# DigitalIO.net
KiCad netlist of a schematic drawn in EAGLE
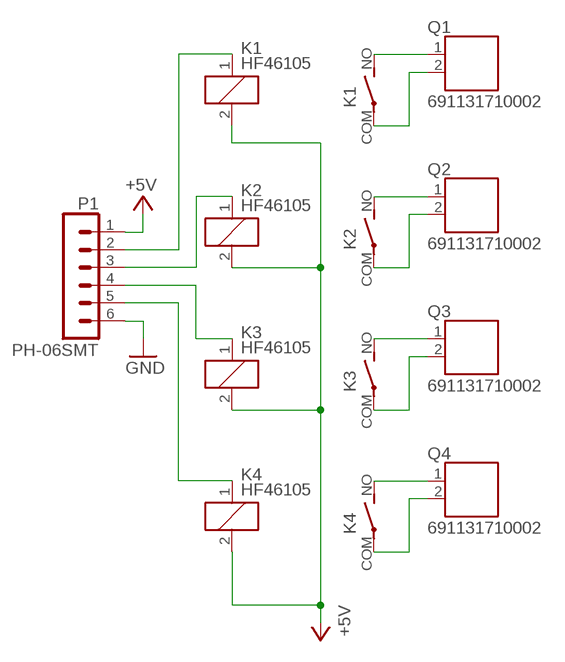
[diagram p0: schematic, sheet 1]

(export (version "E")
  (design (tool "Eeschema 10.0.6"))
  (components
    (comp (ref "K1")
      (value "HF46105")
      (footprint "eagle-import:HF46")
      (libsource (lib "eagle-import") (part "HF46?105"))
    )
    (comp (ref "K2")
      (value "HF46105")
      (footprint "eagle-import:HF46")
      (libsource (lib "eagle-import") (part "HF46?105"))
    )
    (comp (ref "K3")
      (value "HF46105")
      (footprint "eagle-import:HF46")
      (libsource (lib "eagle-import") (part "HF46?105"))
    )
    (comp (ref "K4")
      (value "HF46105")
      (footprint "eagle-import:HF46")
      (libsource (lib "eagle-import") (part "HF46?105"))
    )
    (comp (ref "P1")
      (value "PH-06SMT")
      (footprint "eagle-import:S6B-PH-SM4")
      (libsource (lib "eagle-import") (part "PH-06SMT"))
    )
    (comp (ref "Q1")
      (value "691131710002")
      (footprint "eagle-import:691131710002")
      (libsource (lib "eagle-import") (part "691131710002"))
    )
    (comp (ref "Q2")
      (value "691131710002")
      (footprint "eagle-import:691131710002")
      (libsource (lib "eagle-import") (part "691131710002"))
    )
    (comp (ref "Q3")
      (value "691131710002")
      (footprint "eagle-import:691131710002")
      (libsource (lib "eagle-import") (part "691131710002"))
    )
    (comp (ref "Q4")
      (value "691131710002")
      (footprint "eagle-import:691131710002")
      (libsource (lib "eagle-import") (part "691131710002"))
    )
  )
  (nets
    (net (code "1") (name "+5V") (class "Default")
      (node (ref "K1") (pin "2") (pinfunction "2_2") (pintype "passive"))
      (node (ref "K2") (pin "2") (pinfunction "2_2") (pintype "passive"))
      (node (ref "K3") (pin "2") (pinfunction "2_2") (pintype "passive"))
      (node (ref "K4") (pin "2") (pinfunction "2_2") (pintype "passive"))
      (node (ref "P1") (pin "1") (pinfunction "1_1") (pintype "passive"))
    )
    (net (code "2") (name "GND") (class "Default")
      (node (ref "P1") (pin "6") (pinfunction "6_6") (pintype "passive"))
    )
    (net (code "3") (name "Net-(K1-Pad1)") (class "Default")
      (node (ref "K1") (pin "1") (pinfunction "1_1") (pintype "passive"))
      (node (ref "P1") (pin "2") (pinfunction "2_2") (pintype "passive"))
    )
    (net (code "4") (name "Net-(K1B-P)") (class "Default")
      (node (ref "K1") (pin "COM") (pinfunction "P_COM") (pintype "passive"))
      (node (ref "Q1") (pin "2") (pinfunction "2_2") (pintype "passive"))
    )
    (net (code "5") (name "Net-(K1B-S)") (class "Default")
      (node (ref "K1") (pin "NO") (pinfunction "S_NO") (pintype "passive"))
      (node (ref "Q1") (pin "1") (pinfunction "1_1") (pintype "passive"))
    )
    (net (code "6") (name "Net-(K2-Pad1)") (class "Default")
      (node (ref "K2") (pin "1") (pinfunction "1_1") (pintype "passive"))
      (node (ref "P1") (pin "3") (pinfunction "3_3") (pintype "passive"))
    )
    (net (code "7") (name "Net-(K2B-P)") (class "Default")
      (node (ref "K2") (pin "COM") (pinfunction "P_COM") (pintype "passive"))
      (node (ref "Q2") (pin "2") (pinfunction "2_2") (pintype "passive"))
    )
    (net (code "8") (name "Net-(K2B-S)") (class "Default")
      (node (ref "K2") (pin "NO") (pinfunction "S_NO") (pintype "passive"))
      (node (ref "Q2") (pin "1") (pinfunction "1_1") (pintype "passive"))
    )
    (net (code "9") (name "Net-(K3-Pad1)") (class "Default")
      (node (ref "K3") (pin "1") (pinfunction "1_1") (pintype "passive"))
      (node (ref "P1") (pin "4") (pinfunction "4_4") (pintype "passive"))
    )
    (net (code "10") (name "Net-(K3B-P)") (class "Default")
      (node (ref "K3") (pin "COM") (pinfunction "P_COM") (pintype "passive"))
      (node (ref "Q3") (pin "2") (pinfunction "2_2") (pintype "passive"))
    )
    (net (code "11") (name "Net-(K3B-S)") (class "Default")
      (node (ref "K3") (pin "NO") (pinfunction "S_NO") (pintype "passive"))
      (node (ref "Q3") (pin "1") (pinfunction "1_1") (pintype "passive"))
    )
    (net (code "12") (name "Net-(K4-Pad1)") (class "Default")
      (node (ref "K4") (pin "1") (pinfunction "1_1") (pintype "passive"))
      (node (ref "P1") (pin "5") (pinfunction "5_5") (pintype "passive"))
    )
    (net (code "13") (name "Net-(K4B-P)") (class "Default")
      (node (ref "K4") (pin "COM") (pinfunction "P_COM") (pintype "passive"))
      (node (ref "Q4") (pin "2") (pinfunction "2_2") (pintype "passive"))
    )
    (net (code "14") (name "Net-(K4B-S)") (class "Default")
      (node (ref "K4") (pin "NO") (pinfunction "S_NO") (pintype "passive"))
      (node (ref "Q4") (pin "1") (pinfunction "1_1") (pintype "passive"))
    )
  )
)
